# 2leds.net
KiCad netlist of a schematic drawn in EAGLE
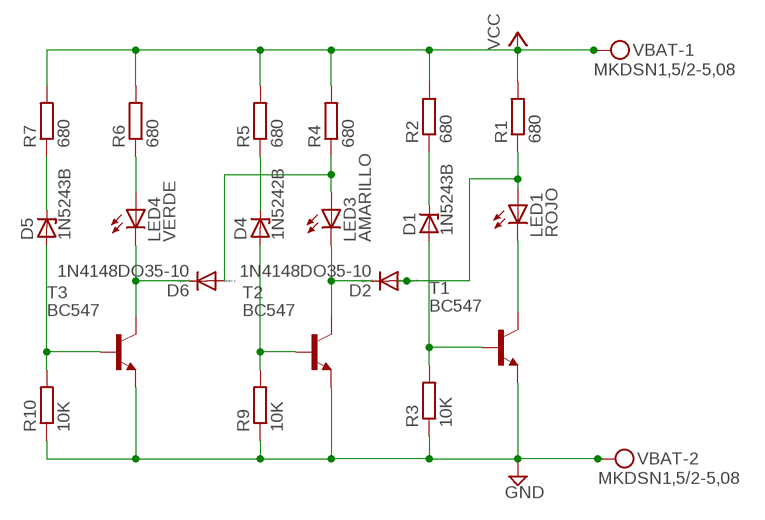
[diagram p0: schematic, sheet 1]

(export (version "E")
  (design (tool "Eeschema 10.0.6"))
  (components
    (comp (ref "D1")
      (value "1N5243B")
      (footprint "eagle-import:DO35Z10")
      (libsource (lib "eagle-import") (part "ZENER-DIODEDO35Z10"))
    )
    (comp (ref "D2")
      (value "1N4148DO35-10")
      (footprint "eagle-import:DO35-10")
      (libsource (lib "eagle-import") (part "1N4148DO35-10"))
    )
    (comp (ref "D4")
      (value "1N5242B")
      (footprint "eagle-import:DO35Z10")
      (libsource (lib "eagle-import") (part "ZENER-DIODEDO35Z10"))
    )
    (comp (ref "D5")
      (value "1N5243B")
      (footprint "eagle-import:DO35Z10")
      (libsource (lib "eagle-import") (part "ZENER-DIODEDO35Z10"))
    )
    (comp (ref "D6")
      (value "1N4148DO35-10")
      (footprint "eagle-import:DO35-10")
      (libsource (lib "eagle-import") (part "1N4148DO35-10"))
    )
    (comp (ref "LED1")
      (value "ROJO")
      (footprint "eagle-import:LED3MM")
      (libsource (lib "eagle-import") (part "LED3MM"))
    )
    (comp (ref "LED3")
      (value "AMARILLO")
      (footprint "eagle-import:LED3MM")
      (libsource (lib "eagle-import") (part "LED3MM"))
    )
    (comp (ref "LED4")
      (value "VERDE")
      (footprint "eagle-import:LED3MM")
      (libsource (lib "eagle-import") (part "LED3MM"))
    )
    (comp (ref "R1")
      (value "680")
      (footprint "eagle-import:0207_10")
      (libsource (lib "eagle-import") (part "R-EU_0207/10"))
    )
    (comp (ref "R2")
      (value "680")
      (footprint "eagle-import:0207_10")
      (libsource (lib "eagle-import") (part "R-EU_0207/10"))
    )
    (comp (ref "R3")
      (value "10K")
      (footprint "eagle-import:0207_10")
      (libsource (lib "eagle-import") (part "R-EU_0207/10"))
    )
    (comp (ref "R4")
      (value "680")
      (footprint "eagle-import:0207_10")
      (libsource (lib "eagle-import") (part "R-EU_0207/10"))
    )
    (comp (ref "R5")
      (value "680")
      (footprint "eagle-import:0207_10")
      (libsource (lib "eagle-import") (part "R-EU_0207/10"))
    )
    (comp (ref "R6")
      (value "680")
      (footprint "eagle-import:0207_10")
      (libsource (lib "eagle-import") (part "R-EU_0207/10"))
    )
    (comp (ref "R7")
      (value "680")
      (footprint "eagle-import:0207_10")
      (libsource (lib "eagle-import") (part "R-EU_0207/10"))
    )
    (comp (ref "R9")
      (value "10K")
      (footprint "eagle-import:0207_10")
      (libsource (lib "eagle-import") (part "R-EU_0207/10"))
    )
    (comp (ref "R10")
      (value "10K")
      (footprint "eagle-import:0207_10")
      (libsource (lib "eagle-import") (part "R-EU_0207/10"))
    )
    (comp (ref "T1")
      (value "BC547")
      (footprint "eagle-import:TO92")
      (libsource (lib "eagle-import") (part "BC547"))
    )
    (comp (ref "T2")
      (value "BC547")
      (footprint "eagle-import:TO92")
      (libsource (lib "eagle-import") (part "BC547"))
    )
    (comp (ref "T3")
      (value "BC547")
      (footprint "eagle-import:TO92")
      (libsource (lib "eagle-import") (part "BC547"))
    )
    (comp (ref "VBAT")
      (value "MKDSN1,5/2-5,08")
      (footprint "eagle-import:MKDSN1,5_2-5,08")
      (libsource (lib "eagle-import") (part "MKDSN1,5/2-5,08"))
    )
  )
  (nets
    (net (code "1") (name "GND") (class "Default")
      (node (ref "R10") (pin "1") (pinfunction "1_1") (pintype "passive"))
      (node (ref "R3") (pin "1") (pinfunction "1_1") (pintype "passive"))
      (node (ref "R9") (pin "1") (pinfunction "1_1") (pintype "passive"))
      (node (ref "T1") (pin "1") (pinfunction "E_1") (pintype "passive"))
      (node (ref "T2") (pin "1") (pinfunction "E_1") (pintype "passive"))
      (node (ref "T3") (pin "1") (pinfunction "E_1") (pintype "passive"))
      (node (ref "VBAT") (pin "2") (pinfunction "KL_2") (pintype "passive"))
    )
    (net (code "2") (name "Net-(D1-PadC)") (class "Default")
      (node (ref "D1") (pin "C") (pinfunction "C_C") (pintype "passive"))
      (node (ref "R2") (pin "1") (pinfunction "1_1") (pintype "passive"))
    )
    (net (code "3") (name "Net-(D2-PadA)") (class "Default")
      (node (ref "D2") (pin "A") (pinfunction "A_A") (pintype "passive"))
      (node (ref "LED1") (pin "A") (pinfunction "A_A") (pintype "passive"))
      (node (ref "R1") (pin "1") (pinfunction "1_1") (pintype "passive"))
    )
    (net (code "4") (name "Net-(D4-PadC)") (class "Default")
      (node (ref "D4") (pin "C") (pinfunction "C_C") (pintype "passive"))
      (node (ref "R5") (pin "1") (pinfunction "1_1") (pintype "passive"))
    )
    (net (code "5") (name "Net-(D5-PadC)") (class "Default")
      (node (ref "D5") (pin "C") (pinfunction "C_C") (pintype "passive"))
      (node (ref "R7") (pin "1") (pinfunction "1_1") (pintype "passive"))
    )
    (net (code "6") (name "Net-(D6-PadA)") (class "Default")
      (node (ref "D6") (pin "A") (pinfunction "A_A") (pintype "passive"))
      (node (ref "LED3") (pin "A") (pinfunction "A_A") (pintype "passive"))
      (node (ref "R4") (pin "1") (pinfunction "1_1") (pintype "passive"))
    )
    (net (code "7") (name "Net-(LED1-C)") (class "Default")
      (node (ref "LED1") (pin "K") (pinfunction "C_K") (pintype "passive"))
      (node (ref "T1") (pin "3") (pinfunction "C_3") (pintype "passive"))
    )
    (net (code "8") (name "Net-(LED3-C)") (class "Default")
      (node (ref "D2") (pin "C") (pinfunction "C_C") (pintype "passive"))
      (node (ref "LED3") (pin "K") (pinfunction "C_K") (pintype "passive"))
      (node (ref "T2") (pin "3") (pinfunction "C_3") (pintype "passive"))
    )
    (net (code "9") (name "Net-(LED4-C)") (class "Default")
      (node (ref "D6") (pin "C") (pinfunction "C_C") (pintype "passive"))
      (node (ref "LED4") (pin "K") (pinfunction "C_K") (pintype "passive"))
      (node (ref "T3") (pin "3") (pinfunction "C_3") (pintype "passive"))
    )
    (net (code "10") (name "Net-(LED4-PadA)") (class "Default")
      (node (ref "LED4") (pin "A") (pinfunction "A_A") (pintype "passive"))
      (node (ref "R6") (pin "1") (pinfunction "1_1") (pintype "passive"))
    )
    (net (code "11") (name "Net-(T1-B)") (class "Default")
      (node (ref "D1") (pin "A") (pinfunction "A_A") (pintype "passive"))
      (node (ref "R3") (pin "2") (pinfunction "2_2") (pintype "passive"))
      (node (ref "T1") (pin "2") (pinfunction "B_2") (pintype "passive"))
    )
    (net (code "12") (name "Net-(T2-B)") (class "Default")
      (node (ref "D4") (pin "A") (pinfunction "A_A") (pintype "passive"))
      (node (ref "R9") (pin "2") (pinfunction "2_2") (pintype "passive"))
      (node (ref "T2") (pin "2") (pinfunction "B_2") (pintype "passive"))
    )
    (net (code "13") (name "Net-(T3-B)") (class "Default")
      (node (ref "D5") (pin "A") (pinfunction "A_A") (pintype "passive"))
      (node (ref "R10") (pin "2") (pinfunction "2_2") (pintype "passive"))
      (node (ref "T3") (pin "2") (pinfunction "B_2") (pintype "passive"))
    )
    (net (code "14") (name "VCC") (class "Default")
      (node (ref "R1") (pin "2") (pinfunction "2_2") (pintype "passive"))
      (node (ref "R2") (pin "2") (pinfunction "2_2") (pintype "passive"))
      (node (ref "R4") (pin "2") (pinfunction "2_2") (pintype "passive"))
      (node (ref "R5") (pin "2") (pinfunction "2_2") (pintype "passive"))
      (node (ref "R6") (pin "2") (pinfunction "2_2") (pintype "passive"))
      (node (ref "R7") (pin "2") (pinfunction "2_2") (pintype "passive"))
      (node (ref "VBAT") (pin "1") (pinfunction "KL_1") (pintype "passive"))
    )
  )
)
